# USB.net
KiCad netlist of a schematic drawn in Altium Designer
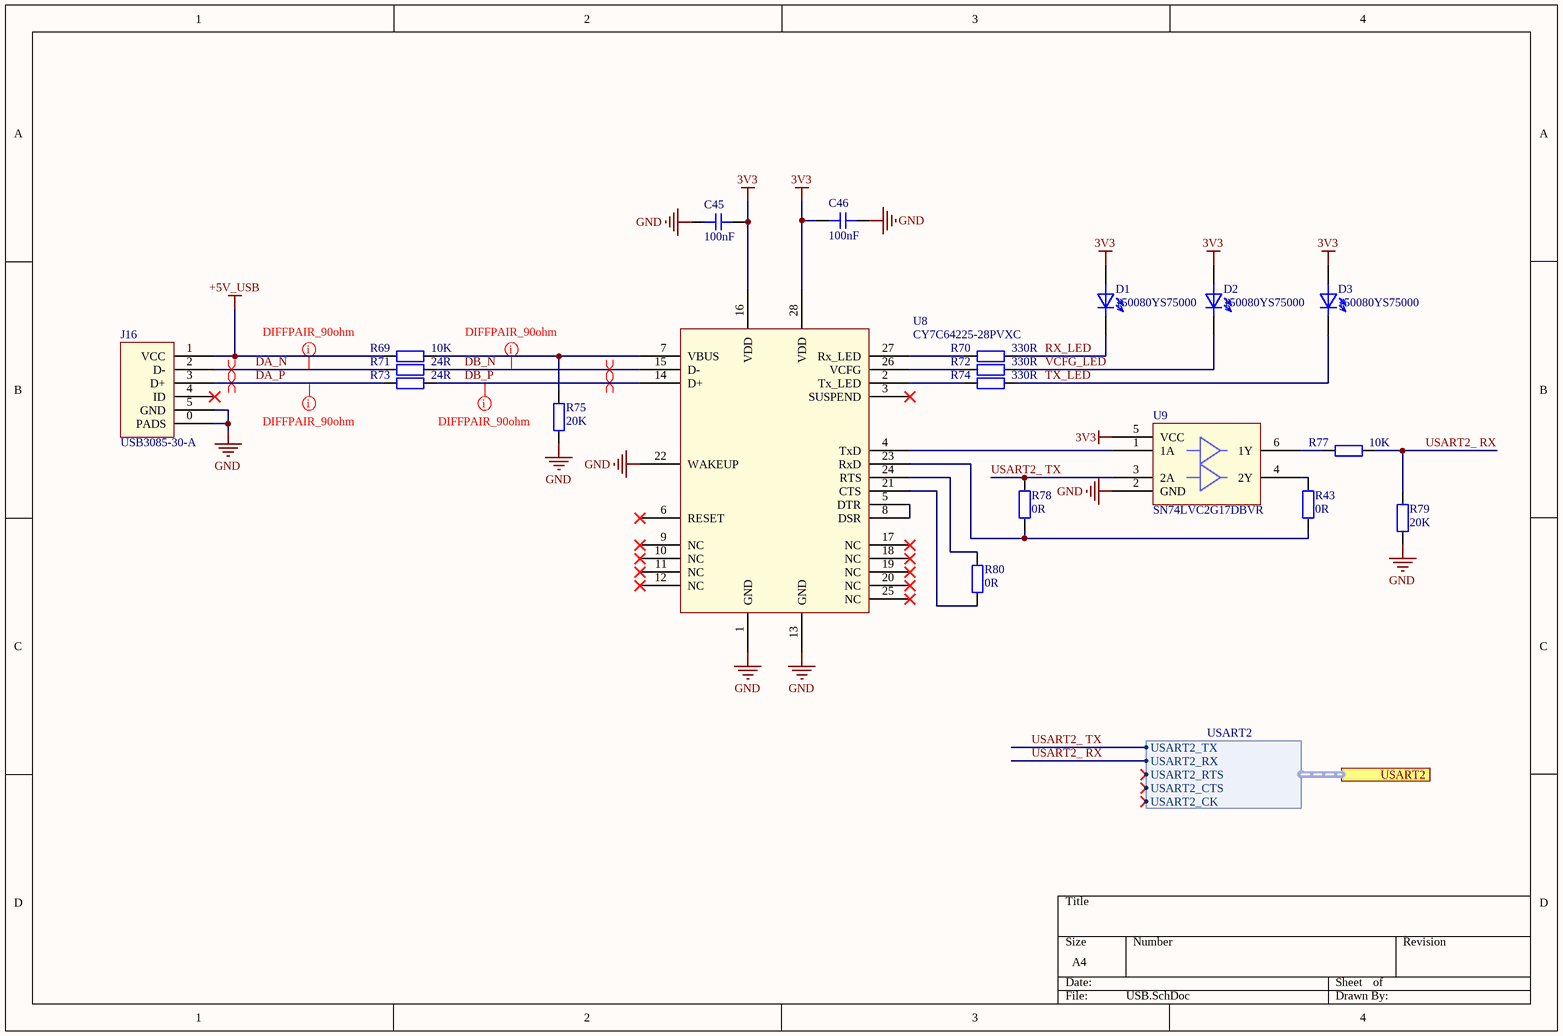
[diagram p0: USB.SchDoc]

(export (version "E")
  (design (tool "Eeschema 10.0.6"))
  (components
    (comp (ref "C45")
      (value "100nF")
      (footprint "Capacitor-0603")
      (fields (field (name "Comment") "C-100nF-0603"))
      (libsource (lib "Components") (part "C-100nF-0603"))
    )
    (comp (ref "C46")
      (value "100nF")
      (footprint "Capacitor-0603")
      (fields (field (name "Comment") "C-100nF-0603"))
      (libsource (lib "Components") (part "C-100nF-0603"))
    )
    (comp (ref "D1")
      (value "150080YS75000")
      (footprint "150080YS75000")
      (libsource (lib "Components") (part "150080YS75000"))
    )
    (comp (ref "D2")
      (value "150080YS75000")
      (footprint "150080YS75000")
      (libsource (lib "Components") (part "150080YS75000"))
    )
    (comp (ref "D3")
      (value "150080YS75000")
      (footprint "150080YS75000")
      (libsource (lib "Components") (part "150080YS75000"))
    )
    (comp (ref "J16")
      (value "USB3085-30-A")
      (footprint "USB3085-30-A")
      (libsource (lib "Components") (part "USB3085-30-A"))
    )
    (comp (ref "R43")
      (value "0R")
      (footprint "Resistor-0603")
      (fields (field (name "Comment") "R-0R-0603"))
      (libsource (lib "Components") (part "R-0R-0603"))
    )
    (comp (ref "R69")
      (value "10K")
      (footprint "Resistor-0603")
      (fields (field (name "Comment") "R-10K-0603"))
      (libsource (lib "Components") (part "R-10K-0603"))
    )
    (comp (ref "R70")
      (value "330R")
      (footprint "Resistor-0603")
      (fields (field (name "Comment") "R-330R-0603"))
      (libsource (lib "Components") (part "R-330R-0603"))
    )
    (comp (ref "R71")
      (value "24R")
      (footprint "Resistor-0603")
      (fields (field (name "Comment") "R-24R-0603"))
      (libsource (lib "Components") (part "R-24R-0603"))
    )
    (comp (ref "R72")
      (value "330R")
      (footprint "Resistor-0603")
      (fields (field (name "Comment") "R-330R-0603"))
      (libsource (lib "Components") (part "R-330R-0603"))
    )
    (comp (ref "R73")
      (value "24R")
      (footprint "Resistor-0603")
      (fields (field (name "Comment") "R-24R-0603"))
      (libsource (lib "Components") (part "R-24R-0603"))
    )
    (comp (ref "R74")
      (value "330R")
      (footprint "Resistor-0603")
      (fields (field (name "Comment") "R-330R-0603"))
      (libsource (lib "Components") (part "R-330R-0603"))
    )
    (comp (ref "R75")
      (value "20K")
      (footprint "Resistor-0603")
      (fields (field (name "Comment") "R-20K-0603"))
      (libsource (lib "Components") (part "R-20K-0603"))
    )
    (comp (ref "R77")
      (value "10K")
      (footprint "Resistor-0603")
      (fields (field (name "Comment") "R-10K-0603"))
      (libsource (lib "Components") (part "R-10K-0603"))
    )
    (comp (ref "R78")
      (value "0R")
      (footprint "Resistor-0603")
      (fields (field (name "Comment") "R-0R-0603"))
      (libsource (lib "Components") (part "R-0R-0603"))
    )
    (comp (ref "R79")
      (value "20K")
      (footprint "Resistor-0603")
      (fields (field (name "Comment") "R-20K-0603"))
      (libsource (lib "Components") (part "R-20K-0603"))
    )
    (comp (ref "R80")
      (value "0R")
      (footprint "Resistor-0603")
      (fields (field (name "Comment") "R-0R-0603"))
      (libsource (lib "Components") (part "R-0R-0603"))
    )
    (comp (ref "U8")
      (value "CY7C64225-28PVXC")
      (footprint "CY7C64225-28PVXC")
      (libsource (lib "Components") (part "CY7C64225-28PVXC"))
    )
    (comp (ref "U9")
      (value "SN74LVC2G17DBVR")
      (footprint "SN74LVC2G17DBVR")
      (libsource (lib "Components") (part "SN74LVC2G17DBVR"))
    )
  )
  (nets
    (net (code "2") (name "+5V_USB") (class "Default")
      (node (ref "J16") (pin "1") (pinfunction "VCC_1") (pintype "passive"))
      (node (ref "R69") (pin "1") (pinfunction "1_1") (pintype "passive"))
    )
    (net (code "3") (name "/DA_N") (class "Default")
      (node (ref "J16") (pin "2") (pinfunction "D-_2") (pintype "passive"))
      (node (ref "R71") (pin "1") (pinfunction "1_1") (pintype "passive"))
    )
    (net (code "4") (name "/DA_P") (class "Default")
      (node (ref "J16") (pin "3") (pinfunction "D+_3") (pintype "passive"))
      (node (ref "R73") (pin "1") (pinfunction "1_1") (pintype "passive"))
    )
    (net (code "5") (name "/DB_N") (class "Default")
      (node (ref "R71") (pin "2") (pinfunction "2_2") (pintype "passive"))
      (node (ref "U8") (pin "15") (pinfunction "D-_15") (pintype "passive"))
    )
    (net (code "6") (name "/DB_P") (class "Default")
      (node (ref "R73") (pin "2") (pinfunction "2_2") (pintype "passive"))
      (node (ref "U8") (pin "14") (pinfunction "D+_14") (pintype "passive"))
    )
    (net (code "7") (name "/RX_LED") (class "Default")
      (node (ref "D1") (pin "1") (pinfunction "1_1") (pintype "passive"))
      (node (ref "R70") (pin "2") (pinfunction "2_2") (pintype "passive"))
    )
    (net (code "8") (name "/TX_LED") (class "Default")
      (node (ref "D3") (pin "1") (pinfunction "1_1") (pintype "passive"))
      (node (ref "R74") (pin "2") (pinfunction "2_2") (pintype "passive"))
    )
    (net (code "9") (name "/USART2_ RX") (class "Default")
      (node (ref "R77") (pin "2") (pinfunction "2_2") (pintype "passive"))
      (node (ref "R79") (pin "2") (pinfunction "2_2") (pintype "passive"))
    )
    (net (code "10") (name "/USART2_ TX") (class "Default")
      (node (ref "R78") (pin "2") (pinfunction "2_2") (pintype "passive"))
      (node (ref "U9") (pin "3") (pinfunction "2A_3") (pintype "passive"))
    )
    (net (code "11") (name "/VCFG_LED") (class "Default")
      (node (ref "D2") (pin "1") (pinfunction "1_1") (pintype "passive"))
      (node (ref "R72") (pin "2") (pinfunction "2_2") (pintype "passive"))
    )
    (net (code "13") (name "3V3") (class "Default")
      (node (ref "C45") (pin "1") (pinfunction "1_1") (pintype "passive"))
      (node (ref "C46") (pin "1") (pinfunction "1_1") (pintype "passive"))
      (node (ref "D1") (pin "2") (pinfunction "2_2") (pintype "passive"))
      (node (ref "D2") (pin "2") (pinfunction "2_2") (pintype "passive"))
      (node (ref "D3") (pin "2") (pinfunction "2_2") (pintype "passive"))
      (node (ref "U8") (pin "16") (pinfunction "VDD_16") (pintype "passive"))
      (node (ref "U8") (pin "28") (pinfunction "VDD_28") (pintype "passive"))
      (node (ref "U9") (pin "5") (pinfunction "VCC_5") (pintype "passive"))
    )
    (net (code "14") (name "GND") (class "Default")
      (node (ref "C45") (pin "2") (pinfunction "2_2") (pintype "passive"))
      (node (ref "C46") (pin "2") (pinfunction "2_2") (pintype "passive"))
      (node (ref "J16") (pin "0") (pinfunction "PADS_0") (pintype "passive"))
      (node (ref "J16") (pin "5") (pinfunction "GND_5") (pintype "passive"))
      (node (ref "R75") (pin "1") (pinfunction "1_1") (pintype "passive"))
      (node (ref "R79") (pin "1") (pinfunction "1_1") (pintype "passive"))
      (node (ref "U8") (pin "1") (pinfunction "GND_1") (pintype "passive"))
      (node (ref "U8") (pin "13") (pinfunction "GND_13") (pintype "passive"))
      (node (ref "U8") (pin "22") (pinfunction "WAKEUP_22") (pintype "passive"))
      (node (ref "U9") (pin "2") (pinfunction "GND_2") (pintype "passive"))
    )
    (net (code "15") (name "Net-(U8-CTS)") (class "Default")
      (node (ref "R80") (pin "1") (pinfunction "1_1") (pintype "passive"))
      (node (ref "U8") (pin "21") (pinfunction "CTS_21") (pintype "passive"))
    )
    (net (code "16") (name "Net-(U8-DSR)") (class "Default")
      (node (ref "U8") (pin "5") (pinfunction "DTR_5") (pintype "passive"))
      (node (ref "U8") (pin "8") (pinfunction "DSR_8") (pintype "passive"))
    )
    (net (code "17") (name "Net-(U8-RTS)") (class "Default")
      (node (ref "R80") (pin "2") (pinfunction "2_2") (pintype "passive"))
      (node (ref "U8") (pin "24") (pinfunction "RTS_24") (pintype "passive"))
    )
    (net (code "18") (name "Net-(U8-RxD)") (class "Default")
      (node (ref "R43") (pin "1") (pinfunction "1_1") (pintype "passive"))
      (node (ref "R78") (pin "1") (pinfunction "1_1") (pintype "passive"))
      (node (ref "U8") (pin "23") (pinfunction "RxD_23") (pintype "passive"))
    )
    (net (code "19") (name "Net-(U8-Rx_LED)") (class "Default")
      (node (ref "R70") (pin "1") (pinfunction "1_1") (pintype "passive"))
      (node (ref "U8") (pin "27") (pinfunction "Rx_LED_27") (pintype "passive"))
    )
    (net (code "20") (name "Net-(U8-TxD)") (class "Default")
      (node (ref "U8") (pin "4") (pinfunction "TxD_4") (pintype "passive"))
      (node (ref "U9") (pin "1") (pinfunction "1A_1") (pintype "passive"))
    )
    (net (code "21") (name "Net-(U8-Tx_LED)") (class "Default")
      (node (ref "R74") (pin "1") (pinfunction "1_1") (pintype "passive"))
      (node (ref "U8") (pin "2") (pinfunction "Tx_LED_2") (pintype "passive"))
    )
    (net (code "22") (name "Net-(U8-VBUS)") (class "Default")
      (node (ref "R69") (pin "2") (pinfunction "2_2") (pintype "passive"))
      (node (ref "R75") (pin "2") (pinfunction "2_2") (pintype "passive"))
      (node (ref "U8") (pin "7") (pinfunction "VBUS_7") (pintype "passive"))
    )
    (net (code "23") (name "Net-(U8-VCFG)") (class "Default")
      (node (ref "R72") (pin "1") (pinfunction "1_1") (pintype "passive"))
      (node (ref "U8") (pin "26") (pinfunction "VCFG_26") (pintype "passive"))
    )
    (net (code "24") (name "Net-(U9-1Y)") (class "Default")
      (node (ref "R77") (pin "1") (pinfunction "1_1") (pintype "passive"))
      (node (ref "U9") (pin "6") (pinfunction "1Y_6") (pintype "passive"))
    )
    (net (code "25") (name "Net-(U9-2Y)") (class "Default")
      (node (ref "R43") (pin "2") (pinfunction "2_2") (pintype "passive"))
      (node (ref "U9") (pin "4") (pinfunction "2Y_4") (pintype "passive"))
    )
    (net (code "26") (name "unconnected-(J16-ID-Pad4)") (class "Default")
      (node (ref "J16") (pin "4") (pinfunction "ID_4") (pintype "passive+no_connect"))
    )
    (net (code "27") (name "unconnected-(U8-NC-Pad9)") (class "Default")
      (node (ref "U8") (pin "9") (pinfunction "NC_9") (pintype "passive+no_connect"))
    )
    (net (code "28") (name "unconnected-(U8-NC-Pad10)") (class "Default")
      (node (ref "U8") (pin "10") (pinfunction "NC_10") (pintype "passive+no_connect"))
    )
    (net (code "29") (name "unconnected-(U8-NC-Pad11)") (class "Default")
      (node (ref "U8") (pin "11") (pinfunction "NC_11") (pintype "passive+no_connect"))
    )
    (net (code "30") (name "unconnected-(U8-NC-Pad12)") (class "Default")
      (node (ref "U8") (pin "12") (pinfunction "NC_12") (pintype "passive+no_connect"))
    )
    (net (code "31") (name "unconnected-(U8-NC-Pad17)") (class "Default")
      (node (ref "U8") (pin "17") (pinfunction "NC_17") (pintype "passive+no_connect"))
    )
    (net (code "32") (name "unconnected-(U8-NC-Pad18)") (class "Default")
      (node (ref "U8") (pin "18") (pinfunction "NC_18") (pintype "passive+no_connect"))
    )
    (net (code "33") (name "unconnected-(U8-NC-Pad19)") (class "Default")
      (node (ref "U8") (pin "19") (pinfunction "NC_19") (pintype "passive+no_connect"))
    )
    (net (code "34") (name "unconnected-(U8-NC-Pad20)") (class "Default")
      (node (ref "U8") (pin "20") (pinfunction "NC_20") (pintype "passive+no_connect"))
    )
    (net (code "35") (name "unconnected-(U8-NC-Pad25)") (class "Default")
      (node (ref "U8") (pin "25") (pinfunction "NC_25") (pintype "passive+no_connect"))
    )
    (net (code "36") (name "unconnected-(U8-RESET-Pad6)") (class "Default")
      (node (ref "U8") (pin "6") (pinfunction "RESET_6") (pintype "passive+no_connect"))
    )
    (net (code "37") (name "unconnected-(U8-SUSPEND-Pad3)") (class "Default")
      (node (ref "U8") (pin "3") (pinfunction "SUSPEND_3") (pintype "passive+no_connect"))
    )
  )
)
